# led_lamp.net
KiCad netlist of a schematic drawn in EAGLE
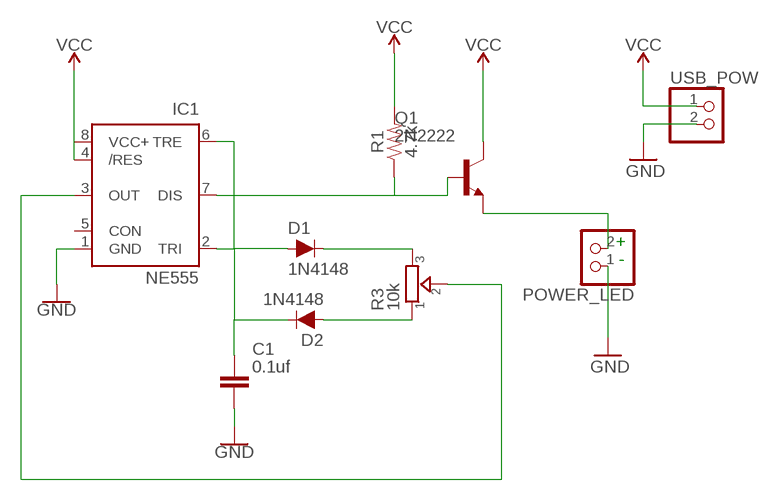
[diagram p0: schematic, sheet 1]

(export (version "E")
  (design (tool "Eeschema 10.0.6"))
  (components
    (comp (ref "C1")
      (value "0.1uf")
      (footprint "eagle-import:C0.1PTH")
      (libsource (lib "eagle-import") (part "CAPACITOR_NPOL-PTH_0.1{dblquote}"))
    )
    (comp (ref "D1")
      (value "1N4148")
      (footprint "eagle-import:DIODE-1N4148")
      (libsource (lib "eagle-import") (part "DIODE-1N4148"))
    )
    (comp (ref "D2")
      (value "1N4148")
      (footprint "eagle-import:DIODE-1N4148")
      (libsource (lib "eagle-import") (part "DIODE-1N4148"))
    )
    (comp (ref "IC1")
      (value "NE555")
      (footprint "eagle-import:DIL-08")
      (fields (field (name "MF") "Arrow Electronics") (field (name "MPN") "NE555N"))
      (libsource (lib "eagle-import") (part "NE555"))
    )
    (comp (ref "POWER_LED")
      (value "PINHD-1X2")
      (footprint "eagle-import:1X02")
      (libsource (lib "eagle-import") (part "PINHD-1X2"))
    )
    (comp (ref "Q1")
      (value "2N2222")
      (footprint "eagle-import:TO92-EBC")
      (libsource (lib "eagle-import") (part "-NPN-TO92-EBC2N2222"))
    )
    (comp (ref "R1")
      (value "4.7k")
      (footprint "eagle-import:AXIAL-0.3-KIT")
      (libsource (lib "eagle-import") (part "10OHM-HORIZ_KIT-1/4W-1%"))
    )
    (comp (ref "R3")
      (value "10k")
      (footprint "eagle-import:TRIMMER_3306F")
      (libsource (lib "eagle-import") (part "TRIMMER-3306F"))
    )
    (comp (ref "USB_POW")
      (value "PINHD-1X2")
      (footprint "eagle-import:1X02")
      (libsource (lib "eagle-import") (part "PINHD-1X2"))
    )
  )
  (nets
    (net (code "1") (name "GND") (class "Default")
      (node (ref "C1") (pin "2") (pinfunction "2_2") (pintype "passive"))
      (node (ref "IC1") (pin "1") (pinfunction "GND_1") (pintype "power_in"))
      (node (ref "POWER_LED") (pin "1") (pinfunction "1_1") (pintype "passive"))
      (node (ref "USB_POW") (pin "2") (pinfunction "2_2") (pintype "passive"))
    )
    (net (code "2") (name "Net-(D1-PadC)") (class "Default")
      (node (ref "D1") (pin "C") (pinfunction "C_C") (pintype "passive"))
      (node (ref "R3") (pin "3") (pinfunction "3_3") (pintype "passive"))
    )
    (net (code "3") (name "Net-(D2-PadA)") (class "Default")
      (node (ref "D2") (pin "A") (pinfunction "A_A") (pintype "passive"))
      (node (ref "R3") (pin "1") (pinfunction "1_1") (pintype "passive"))
    )
    (net (code "4") (name "Net-(IC1-DIS)") (class "Default")
      (node (ref "IC1") (pin "7") (pinfunction "DIS_7") (pintype "input"))
      (node (ref "Q1") (pin "B") (pinfunction "B_B") (pintype "passive"))
      (node (ref "R1") (pin "P$1") (pinfunction "1_P$1") (pintype "passive"))
    )
    (net (code "5") (name "Net-(IC1-OUT)") (class "Default")
      (node (ref "IC1") (pin "3") (pinfunction "OUT_3") (pintype "output"))
      (node (ref "R3") (pin "2") (pinfunction "2_2") (pintype "passive"))
    )
    (net (code "6") (name "Net-(IC1-TRE)") (class "Default")
      (node (ref "C1") (pin "1") (pinfunction "1_1") (pintype "passive"))
      (node (ref "D1") (pin "A") (pinfunction "A_A") (pintype "passive"))
      (node (ref "D2") (pin "C") (pinfunction "C_C") (pintype "passive"))
      (node (ref "IC1") (pin "2") (pinfunction "TRI_2") (pintype "input"))
      (node (ref "IC1") (pin "6") (pinfunction "TRE_6") (pintype "input"))
    )
    (net (code "7") (name "Net-(POWER_LED-Pad2)") (class "Default")
      (node (ref "POWER_LED") (pin "2") (pinfunction "2_2") (pintype "passive"))
      (node (ref "Q1") (pin "E") (pinfunction "E_E") (pintype "passive"))
    )
    (net (code "8") (name "VCC") (class "Default")
      (node (ref "IC1") (pin "4") (pinfunction "/RES_4") (pintype "input"))
      (node (ref "IC1") (pin "8") (pinfunction "VCC+_8") (pintype "power_in"))
      (node (ref "Q1") (pin "C") (pinfunction "C_C") (pintype "passive"))
      (node (ref "R1") (pin "P$2") (pinfunction "2_P$2") (pintype "passive"))
      (node (ref "USB_POW") (pin "1") (pinfunction "1_1") (pintype "passive"))
    )
    (net (code "9") (name "unconnected-(IC1-CON-Pad5)") (class "Default")
      (node (ref "IC1") (pin "5") (pinfunction "CON_5") (pintype "input"))
    )
  )
)
